# MAIN_MCU_LORA.net
KiCad netlist of a schematic drawn in Altium Designer
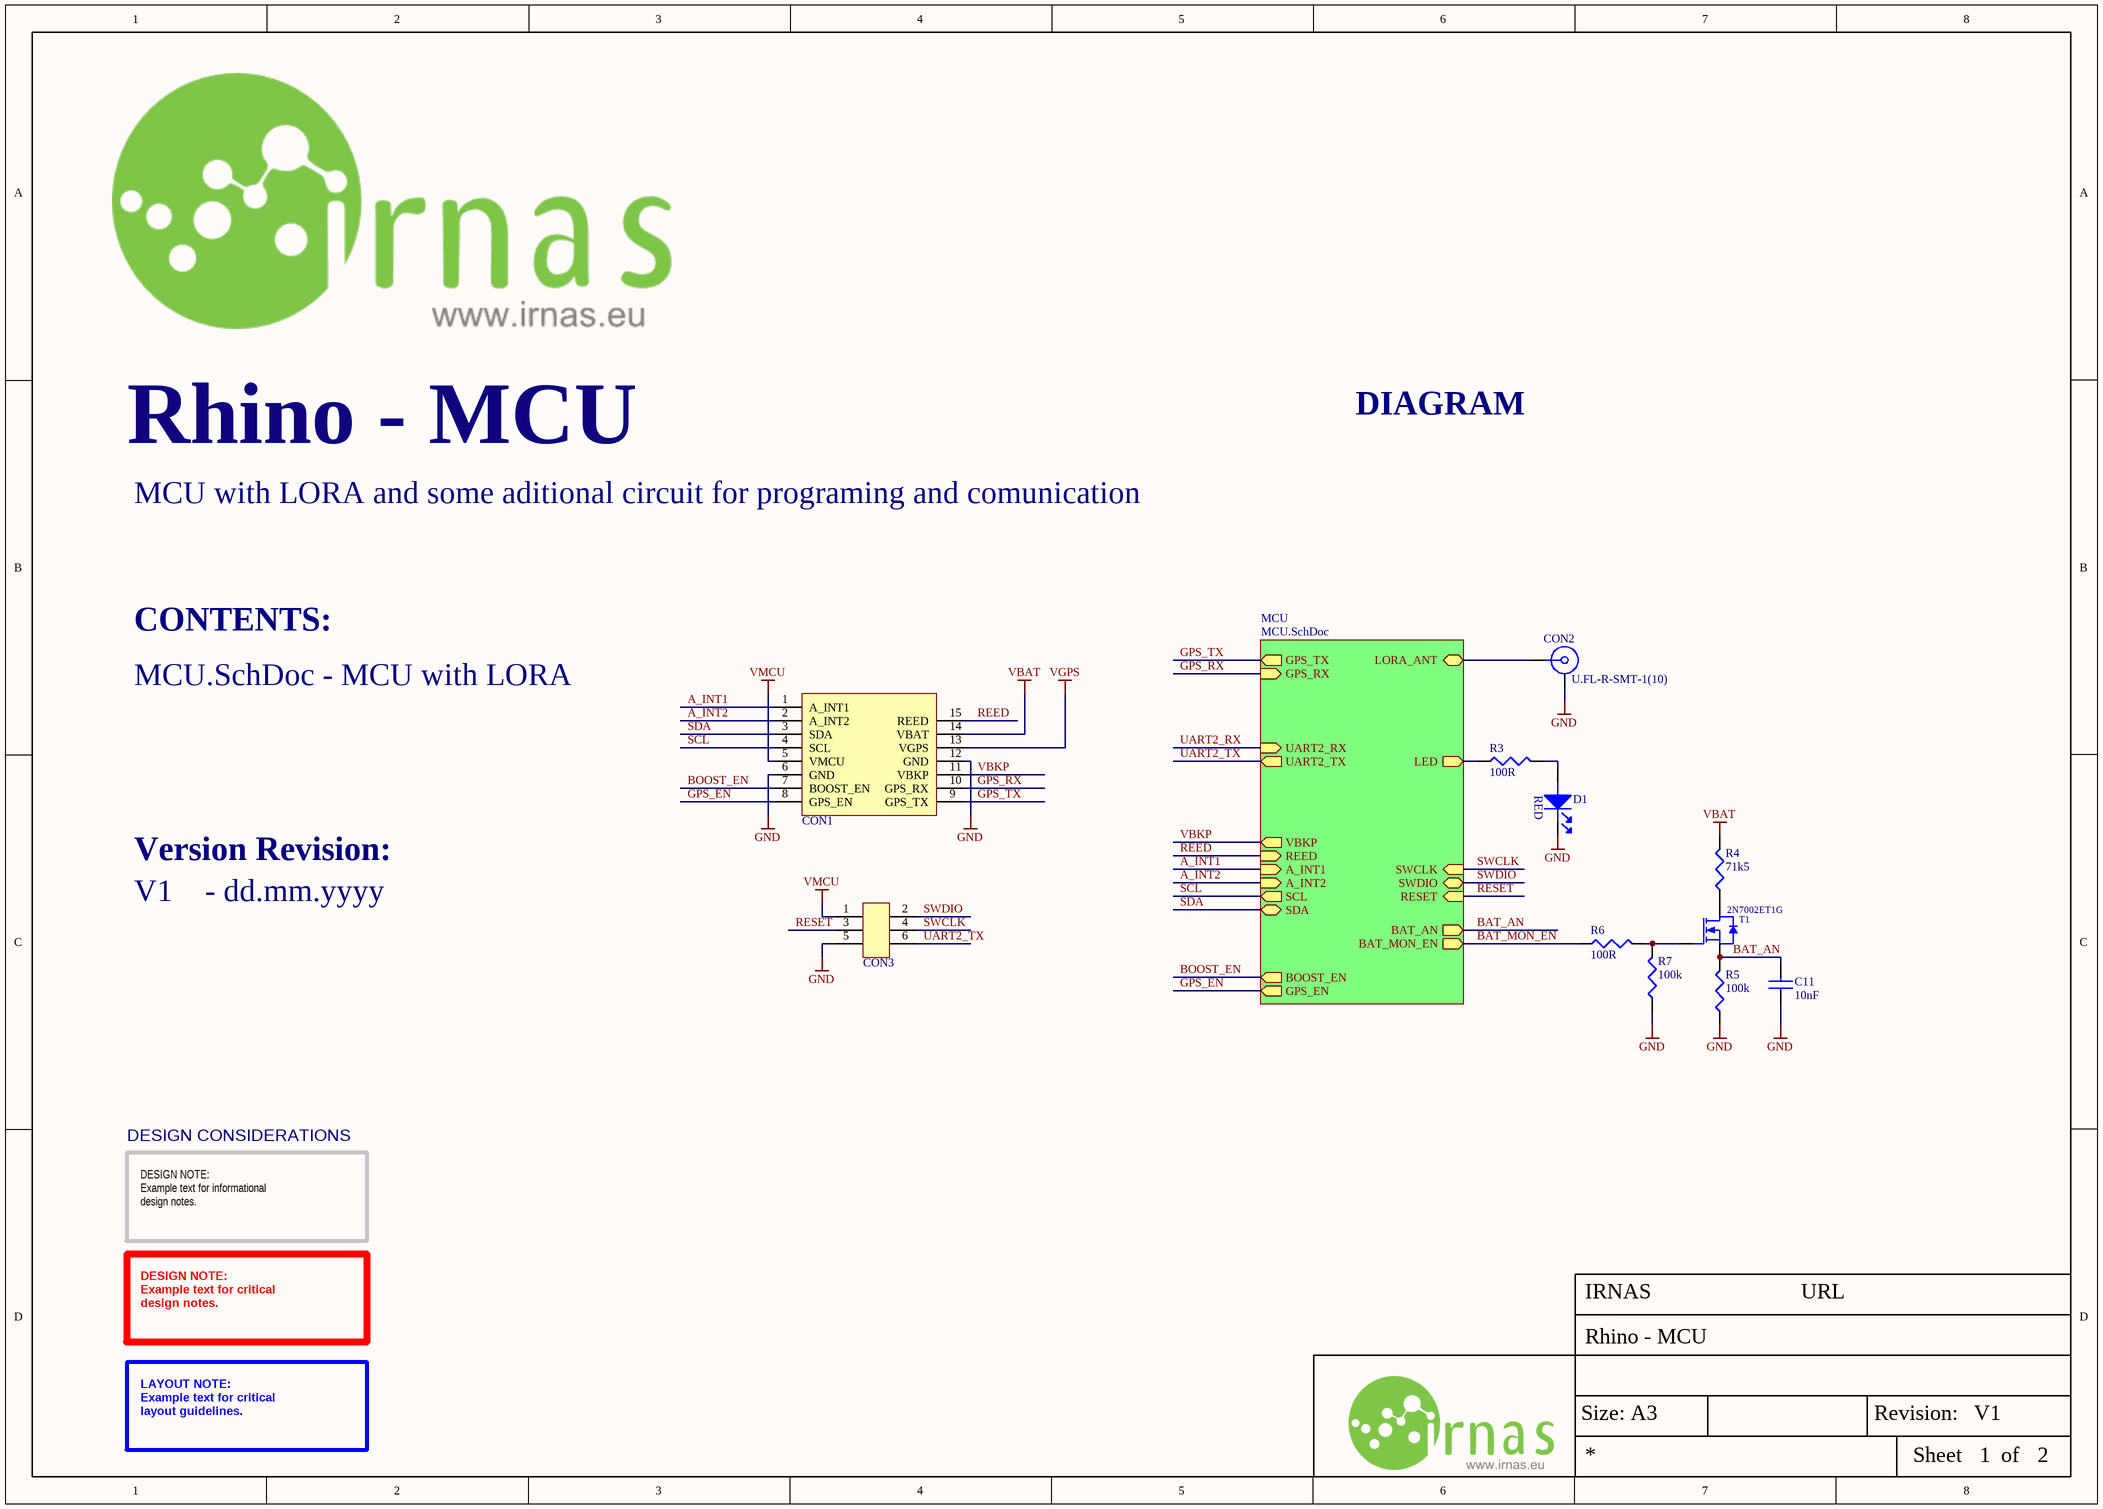
[diagram p0: MAIN_MCU_LORA.SchDoc]

(export (version "E")
  (design (tool "Eeschema 10.0.6"))
  (components
    (comp (ref "C11")
      (value "10nF")
      (footprint "CAP0402")
      (description "CAP CER 10000PF 16V X7R 0402")
      (fields
        (field (name "MANUFACTURER") "Murata")
        (field (name "MANUFACTURER PART NUMBER") "GRM155R71C103KA01D")
      )
      (libsource (lib "Passive") (part "C - 10nF/0402"))
    )
    (comp (ref "CON1")
      (value "Between PCB connection")
      (footprint "SmartParks_Rhino")
      (libsource (lib "Connectors") (part "SmartParks_Rhino"))
    )
    (comp (ref "CON2")
      (value "U.FL-R-SMT-1(10)")
      (footprint "ufl connector smd")
      (description "RF / Coaxial Connector, U.FL Coaxial, Straight Jack, Surface Mount Vertical, 50 ohm, Brass")
      (fields (field (name "MANUFACTURER") "Hirose"))
      (libsource (lib "Connectors") (part "U.FL-R-SMT-1(10)"))
    )
    (comp (ref "CON3")
      (value "Tag connect")
      (footprint "TC2030-IDC-NL")
      (libsource (lib "Connectors") (part "tag connecot 6 pin"))
    )
    (comp (ref "D1")
      (value "LED RED")
      (footprint "LED0603")
      (description "BROADCOM LIMITED - HSMS-C190 - LED, RED, 10MCD, 626NM")
      (fields
        (field (name "MANUFACTURER") "BROADCOM LIMITED")
        (field (name "MANUFACTURER PART NUMBER") "HSMS-C190")
      )
      (libsource (lib "Active") (part "LED - LED RED"))
    )
    (comp (ref "R3")
      (value "100R")
      (footprint "RES0402")
      (fields
        (field (name "MANUFACTURER") "Multicomp")
        (field (name "MANUFACTURER PART NUMBER") "MCMR04X1000FTL")
        (field (name "TOLERANCE") "1%")
      )
      (libsource (lib "Passive") (part "R - 100R/0402"))
    )
    (comp (ref "R4")
      (value "71k5")
      (footprint "RES0402")
      (fields
        (field (name "MANUFACTURER") "Multicomp")
        (field (name "MANUFACTURER PART NUMBER") "MCMR04X7152FTL")
        (field (name "TOLERANCE") "1%")
      )
      (libsource (lib "Passive") (part "R - 71k5/0402"))
    )
    (comp (ref "R5")
      (value "100k")
      (footprint "RES0402")
      (description "MULTICOMP   MCWR04X1003FTL   RES, THICK FILM, 100KOHM, 1%, 0.0625W")
      (fields
        (field (name "MANUFACTURER") "Multicomp")
        (field (name "MANUFACTURER PART NUMBER") "MCWR04X1003FTL")
      )
      (libsource (lib "Passive") (part "R - 100k/0402"))
    )
    (comp (ref "R6")
      (value "100R")
      (footprint "RES0402")
      (fields
        (field (name "MANUFACTURER") "Multicomp")
        (field (name "MANUFACTURER PART NUMBER") "MCMR04X1000FTL")
        (field (name "TOLERANCE") "1%")
      )
      (libsource (lib "Passive") (part "R - 100R/0402"))
    )
    (comp (ref "R7")
      (value "100k")
      (footprint "RES0402")
      (description "MULTICOMP   MCWR04X1003FTL   RES, THICK FILM, 100KOHM, 1%, 0.0625W")
      (fields
        (field (name "MANUFACTURER") "Multicomp")
        (field (name "MANUFACTURER PART NUMBER") "MCWR04X1003FTL")
      )
      (libsource (lib "Passive") (part "R - 100k/0402"))
    )
    (comp (ref "T1")
      (value "2N7002ET1G")
      (footprint "Active:SOT23-3AL")
      (description "MOSFET Transistor, N Channel, 310 mA, 60 V, 0.86 ohm, 10 V, 1 V")
      (fields (field (name "AUTHOR") "Ciril Golob"))
      (libsource (lib "Active") (part "T_M - 2N7002ET1G"))
    )
  )
  (nets
    (net (code "1") (name "/A_INT1") (class "Default")
      (node (ref "CON1") (pin "1") (pinfunction "A_INT1_1") (pintype "passive"))
    )
    (net (code "2") (name "/A_INT2") (class "Default")
      (node (ref "CON1") (pin "2") (pinfunction "A_INT2_2") (pintype "passive"))
    )
    (net (code "3") (name "/BAT_AN") (class "Default")
      (node (ref "C11") (pin "2") (pinfunction "2_2") (pintype "passive"))
      (node (ref "R5") (pin "2") (pinfunction "2_2") (pintype "passive"))
      (node (ref "T1") (pin "2") (pinfunction "S_2") (pintype "passive"))
    )
    (net (code "4") (name "/BAT_MON_EN") (class "Default")
      (node (ref "R6") (pin "1") (pinfunction "1_1") (pintype "passive"))
    )
    (net (code "5") (name "/BOOST_EN") (class "Default")
      (node (ref "CON1") (pin "7") (pinfunction "BOOST_EN_7") (pintype "passive"))
    )
    (net (code "6") (name "/GPS_EN") (class "Default")
      (node (ref "CON1") (pin "8") (pinfunction "GPS_EN_8") (pintype "passive"))
    )
    (net (code "7") (name "/GPS_RX") (class "Default")
      (node (ref "CON1") (pin "10") (pinfunction "GPS_RX_10") (pintype "passive"))
    )
    (net (code "8") (name "/GPS_TX") (class "Default")
      (node (ref "CON1") (pin "9") (pinfunction "GPS_TX_9") (pintype "passive"))
    )
    (net (code "9") (name "/LED") (class "Default")
      (node (ref "R3") (pin "1") (pinfunction "1_1") (pintype "passive"))
    )
    (net (code "10") (name "/LORA_ANT") (class "Default")
      (node (ref "CON2") (pin "1") (pinfunction "1_1") (pintype "open_collector"))
    )
    (net (code "11") (name "/REED") (class "Default")
      (node (ref "CON1") (pin "15") (pinfunction "REED_15") (pintype "passive"))
    )
    (net (code "12") (name "/RESET") (class "Default")
      (node (ref "CON3") (pin "3") (pinfunction "3_3") (pintype "open_collector"))
    )
    (net (code "13") (name "/SCL") (class "Default")
      (node (ref "CON1") (pin "4") (pinfunction "SCL_4") (pintype "passive"))
    )
    (net (code "14") (name "/SDA") (class "Default")
      (node (ref "CON1") (pin "3") (pinfunction "SDA_3") (pintype "passive"))
    )
    (net (code "15") (name "/SWCLK") (class "Default")
      (node (ref "CON3") (pin "4") (pinfunction "4_4") (pintype "open_collector"))
    )
    (net (code "16") (name "/SWDIO") (class "Default")
      (node (ref "CON3") (pin "2") (pinfunction "2_2") (pintype "open_collector"))
    )
    (net (code "18") (name "/UART2_TX") (class "Default")
      (node (ref "CON3") (pin "6") (pinfunction "6_6") (pintype "passive"))
    )
    (net (code "19") (name "/VBKP") (class "Default")
      (node (ref "CON1") (pin "11") (pinfunction "VBKP_11") (pintype "passive"))
    )
    (net (code "20") (name "GND") (class "Default")
      (node (ref "C11") (pin "1") (pinfunction "1_1") (pintype "passive"))
      (node (ref "CON1") (pin "12") (pinfunction "GND_12") (pintype "passive"))
      (node (ref "CON1") (pin "6") (pinfunction "GND_6") (pintype "passive"))
      (node (ref "CON2") (pin "2") (pinfunction "2_2") (pintype "open_collector"))
      (node (ref "CON3") (pin "5") (pinfunction "5_5") (pintype "open_collector"))
      (node (ref "D1") (pin "1") (pinfunction "cathode_1") (pintype "passive"))
      (node (ref "R5") (pin "1") (pinfunction "1_1") (pintype "passive"))
      (node (ref "R7") (pin "1") (pinfunction "1_1") (pintype "passive"))
    )
    (net (code "21") (name "Net-(D1-ANODE)") (class "Default")
      (node (ref "D1") (pin "2") (pinfunction "ANODE_2") (pintype "passive"))
      (node (ref "R3") (pin "2") (pinfunction "2_2") (pintype "passive"))
    )
    (net (code "22") (name "Net-(T1-D)") (class "Default")
      (node (ref "R4") (pin "1") (pinfunction "1_1") (pintype "passive"))
      (node (ref "T1") (pin "3") (pinfunction "D_3") (pintype "passive"))
    )
    (net (code "23") (name "Net-(T1-G)") (class "Default")
      (node (ref "R6") (pin "2") (pinfunction "2_2") (pintype "passive"))
      (node (ref "R7") (pin "2") (pinfunction "2_2") (pintype "passive"))
      (node (ref "T1") (pin "1") (pinfunction "G_1") (pintype "passive"))
    )
    (net (code "24") (name "VBAT") (class "Default")
      (node (ref "CON1") (pin "14") (pinfunction "VBAT_14") (pintype "passive"))
      (node (ref "R4") (pin "2") (pinfunction "2_2") (pintype "passive"))
    )
    (net (code "25") (name "VGPS") (class "Default")
      (node (ref "CON1") (pin "13") (pinfunction "VGPS_13") (pintype "passive"))
    )
    (net (code "26") (name "VMCU") (class "Default")
      (node (ref "CON1") (pin "5") (pinfunction "VMCU_5") (pintype "passive"))
      (node (ref "CON3") (pin "1") (pinfunction "1_1") (pintype "open_collector"))
    )
  )
)
